# Sheet5.net
KiCad netlist of a schematic drawn in Altium Designer
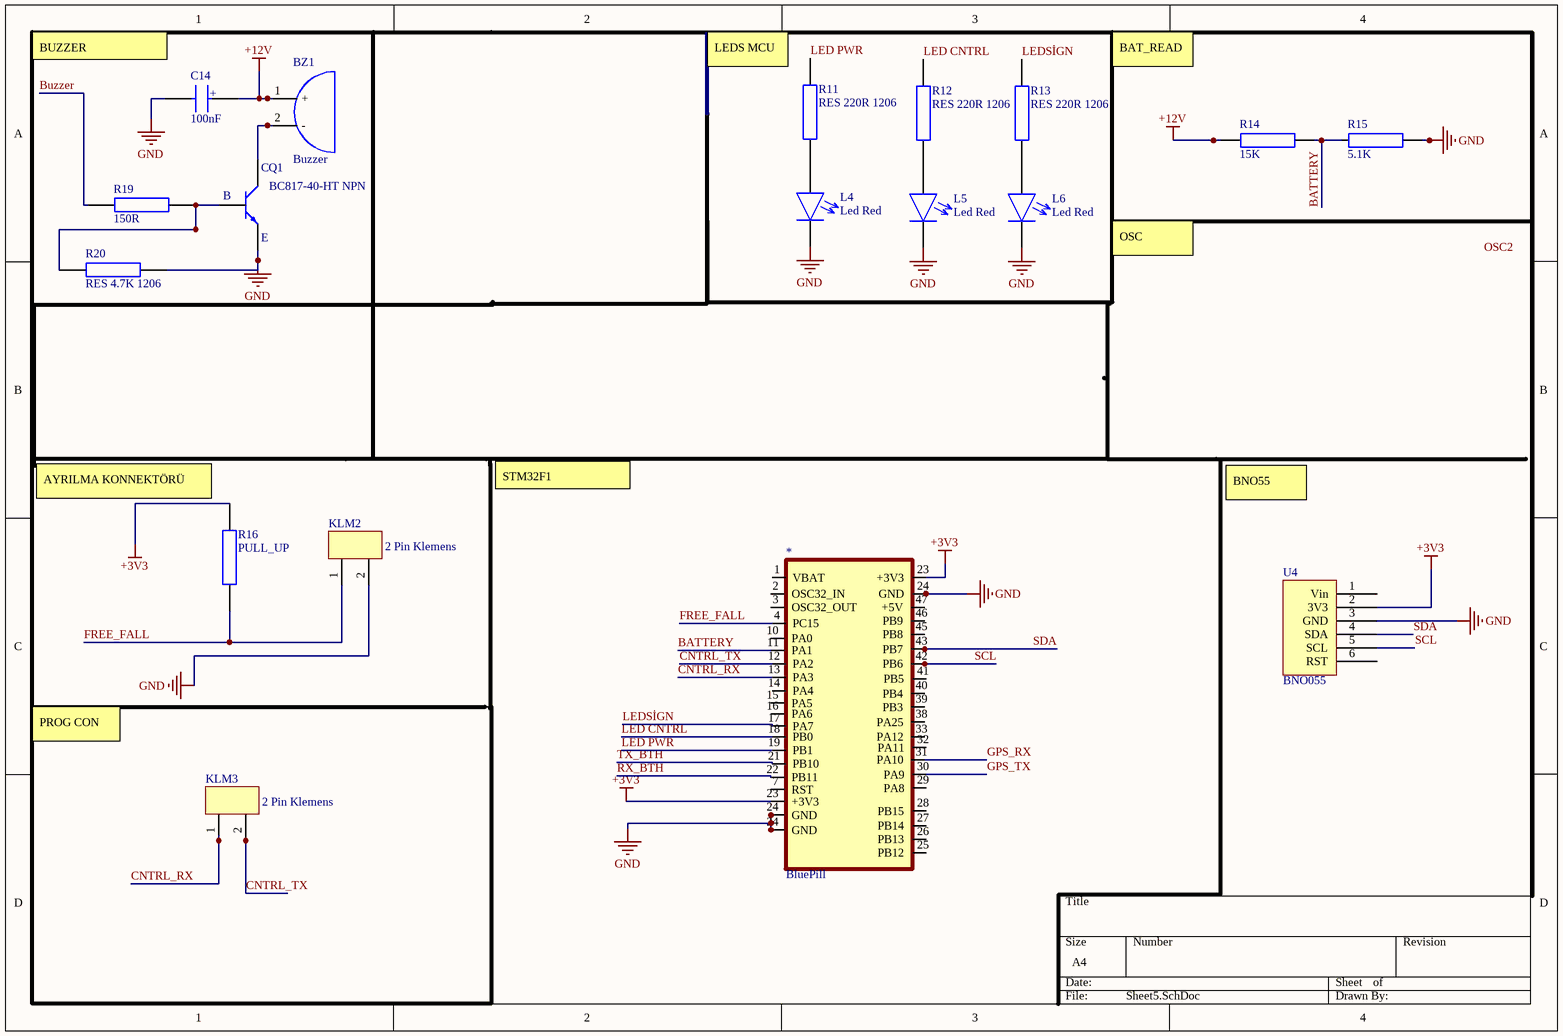
[diagram p0: Sheet5.SchDoc]

(export (version "E")
  (design (tool "Eeschema 10.0.6"))
  (components
    (comp (ref "*") (value "BluePill") (footprint "BLUEPILL") (libsource (lib "Schlib") (part "BluePill")))
    (comp (ref "BZ1")
      (value "Buzzer")
      (footprint "CMI-9605IC")
      (fields (field (name "DESIGNED BY") "Ahmet Azboy"))
      (libsource (lib "Udemy_Schlib1") (part "BUZZER"))
    )
    (comp (ref "C14")
      (value "100nF")
      (footprint "CAP_805")
      (description "0805 smd")
      (libsource (lib "Udemy_Schlib1") (part "CAP 100nF 0805"))
    )
    (comp (ref "KLM2")
      (value "2 Pin Klemens")
      (footprint "5.08mm-2 pin")
      (description "5.08mm 2 pin klemens")
      (libsource (lib "Udemy_Schlib1") (part "2 Pin Klemens"))
    )
    (comp (ref "KLM3")
      (value "2 Pin Klemens")
      (footprint "5.08mm-2 pin")
      (description "5.08mm 2 pin klemens")
      (libsource (lib "Udemy_Schlib1") (part "2 Pin Klemens"))
    )
    (comp (ref "L4")
      (value "Led Red")
      (footprint "Led 1206")
      (libsource (lib "Udemy_Schlib1") (part "Led Red"))
    )
    (comp (ref "L5")
      (value "Led Red")
      (footprint "Led 1206")
      (libsource (lib "Udemy_Schlib1") (part "Led Red"))
    )
    (comp (ref "L6")
      (value "Led Red")
      (footprint "Led 1206")
      (libsource (lib "Udemy_Schlib1") (part "Led Red"))
    )
    (comp (ref "Q1")
      (value "BC817-40-HT NPN")
      (footprint "SOT-23")
      (fields (field (name "VOLTAGE") "45V"))
      (libsource (lib "Udemy_Schlib1") (part "BC817-40-HT NPN"))
    )
    (comp (ref "R11")
      (value "RES 220R 1206")
      (footprint "RES_1206")
      (libsource (lib "Udemy_Schlib1") (part "RES 220R 1206"))
    )
    (comp (ref "R12")
      (value "RES 220R 1206")
      (footprint "RES_1206")
      (libsource (lib "Udemy_Schlib1") (part "RES 220R 1206"))
    )
    (comp (ref "R13")
      (value "RES 220R 1206")
      (footprint "RES_1206")
      (libsource (lib "Udemy_Schlib1") (part "RES 220R 1206"))
    )
    (comp (ref "R14")
      (value "15K")
      (footprint "RES_1206")
      (libsource (lib "Udemy_Schlib1") (part "RES 1K 1206"))
    )
    (comp (ref "R15")
      (value "5.1K")
      (footprint "RES_1206")
      (libsource (lib "Udemy_Schlib1") (part "RES 1K 1206"))
    )
    (comp (ref "R16")
      (value "PULL_UP")
      (footprint "RES_1206")
      (libsource (lib "Udemy_Schlib1") (part "RES 4.7K 1206"))
    )
    (comp (ref "R19")
      (value "150R")
      (footprint "RES_1206")
      (libsource (lib "Udemy_Schlib1") (part "RES 4.7K 1206"))
    )
    (comp (ref "R20")
      (value "RES 4.7K 1206")
      (footprint "RES_1206")
      (libsource (lib "Udemy_Schlib1") (part "RES 4.7K 1206"))
    )
    (comp (ref "U4") (value "BNO055") (footprint "BNO055") (libsource (lib "Schlib") (part "BNO055")))
  )
  (nets
    (net (code "1") (name "+3V3") (class "Default")
      (node (ref "*") (pin "23") (pinfunction "+3V3_23") (pintype "passive"))
      (node (ref "R16") (pin "2") (pintype "passive"))
      (node (ref "U4") (pin "2") (pinfunction "3V3_2") (pintype "passive"))
    )
    (net (code "2") (name "+12V") (class "Default")
      (node (ref "BZ1") (pin "1") (pinfunction "+_1") (pintype "passive"))
      (node (ref "C14") (pin "1") (pinfunction "1_1") (pintype "passive"))
      (node (ref "R14") (pin "1") (pintype "passive"))
    )
    (net (code "3") (name "/BATTERY") (class "Default")
      (node (ref "*") (pin "11") (pinfunction "PA1_11") (pintype "passive"))
      (node (ref "R14") (pin "2") (pintype "passive"))
      (node (ref "R15") (pin "1") (pintype "passive"))
    )
    (net (code "4") (name "/Buzzer") (class "Default") (node (ref "R19") (pin "2") (pintype "passive")))
    (net (code "5") (name "/CNTRL_RX") (class "Default")
      (node (ref "*") (pin "13") (pinfunction "PA3_13") (pintype "passive"))
      (node (ref "KLM3") (pin "1") (pintype "passive"))
    )
    (net (code "6") (name "/CNTRL_TX") (class "Default")
      (node (ref "*") (pin "12") (pinfunction "PA2_12") (pintype "passive"))
      (node (ref "KLM3") (pin "2") (pintype "passive"))
    )
    (net (code "7") (name "/FREE_FALL") (class "Default")
      (node (ref "*") (pin "4") (pinfunction "PC15_4") (pintype "passive"))
      (node (ref "KLM2") (pin "1") (pintype "passive"))
      (node (ref "R16") (pin "1") (pintype "passive"))
    )
    (net (code "8") (name "/GPS_RX") (class "Default")
      (node (ref "*") (pin "31") (pinfunction "PA10_31") (pintype "passive"))
    )
    (net (code "9") (name "/GPS_TX") (class "Default")
      (node (ref "*") (pin "30") (pinfunction "PA9_30") (pintype "passive"))
    )
    (net (code "10") (name "/LED CNTRL") (class "Default")
      (node (ref "*") (pin "18") (pinfunction "PB0_18") (pintype "passive"))
      (node (ref "R12") (pin "2") (pintype "passive"))
    )
    (net (code "11") (name "/LED PWR") (class "Default")
      (node (ref "*") (pin "19") (pinfunction "PB1_19") (pintype "passive"))
      (node (ref "R11") (pin "2") (pintype "passive"))
    )
    (net (code "12") (name "/LEDSİGN") (class "Default")
      (node (ref "*") (pin "17") (pinfunction "PA7_17") (pintype "passive"))
      (node (ref "R13") (pin "2") (pintype "passive"))
    )
    (net (code "14") (name "/RX_BTH") (class "Default")
      (node (ref "*") (pin "22") (pinfunction "PB11_22") (pintype "passive"))
    )
    (net (code "15") (name "/SCL") (class "Default")
      (node (ref "*") (pin "42") (pinfunction "PB6_42") (pintype "passive"))
      (node (ref "U4") (pin "5") (pinfunction "SCL_5") (pintype "passive"))
    )
    (net (code "16") (name "/SDA") (class "Default")
      (node (ref "*") (pin "43") (pinfunction "PB7_43") (pintype "passive"))
      (node (ref "U4") (pin "4") (pinfunction "SDA_4") (pintype "passive"))
    )
    (net (code "17") (name "/TX_BTH") (class "Default")
      (node (ref "*") (pin "21") (pinfunction "PB10_21") (pintype "passive"))
    )
    (net (code "18") (name "GND") (class "Default")
      (node (ref "*") (pin "24") (pinfunction "GND_24") (pintype "passive"))
      (node (ref "C14") (pin "2") (pinfunction "2_2") (pintype "passive"))
      (node (ref "KLM2") (pin "2") (pintype "passive"))
      (node (ref "L4") (pin "2") (pintype "passive"))
      (node (ref "L5") (pin "2") (pintype "passive"))
      (node (ref "L6") (pin "2") (pintype "passive"))
      (node (ref "Q1") (pin "2") (pintype "passive"))
      (node (ref "R15") (pin "2") (pintype "passive"))
      (node (ref "R20") (pin "1") (pintype "passive"))
      (node (ref "U4") (pin "3") (pinfunction "GND_3") (pintype "passive"))
    )
    (net (code "19") (name "Net-(BZ1--)") (class "Default")
      (node (ref "BZ1") (pin "2") (pinfunction "-_2") (pintype "passive"))
      (node (ref "Q1") (pin "3") (pintype "passive"))
    )
    (net (code "20") (name "Net-(L4-Pad1)") (class "Default")
      (node (ref "L4") (pin "1") (pintype "passive"))
      (node (ref "R11") (pin "1") (pintype "passive"))
    )
    (net (code "21") (name "Net-(L5-Pad1)") (class "Default")
      (node (ref "L5") (pin "1") (pintype "passive"))
      (node (ref "R12") (pin "1") (pintype "passive"))
    )
    (net (code "22") (name "Net-(L6-Pad1)") (class "Default")
      (node (ref "L6") (pin "1") (pintype "passive"))
      (node (ref "R13") (pin "1") (pintype "passive"))
    )
    (net (code "23") (name "Net-(Q1-Pad1)") (class "Default")
      (node (ref "Q1") (pin "1") (pintype "passive"))
      (node (ref "R19") (pin "1") (pintype "passive"))
      (node (ref "R20") (pin "2") (pintype "passive"))
    )
    (net (code "24") (name "unconnected-(*-+5V-Pad47)") (class "Default")
      (node (ref "*") (pin "47") (pinfunction "+5V_47") (pintype "passive"))
    )
    (net (code "25") (name "unconnected-(*-OSC32_IN-Pad2)") (class "Default")
      (node (ref "*") (pin "2") (pinfunction "OSC32_IN_2") (pintype "passive"))
    )
    (net (code "26") (name "unconnected-(*-OSC32_OUT-Pad3)") (class "Default")
      (node (ref "*") (pin "3") (pinfunction "OSC32_OUT_3") (pintype "passive"))
    )
    (net (code "27") (name "unconnected-(*-PA0-Pad10)") (class "Default")
      (node (ref "*") (pin "10") (pinfunction "PA0_10") (pintype "passive"))
    )
    (net (code "28") (name "unconnected-(*-PA4-Pad14)") (class "Default")
      (node (ref "*") (pin "14") (pinfunction "PA4_14") (pintype "passive"))
    )
    (net (code "29") (name "unconnected-(*-PA5-Pad15)") (class "Default")
      (node (ref "*") (pin "15") (pinfunction "PA5_15") (pintype "passive"))
    )
    (net (code "30") (name "unconnected-(*-PA6-Pad16)") (class "Default")
      (node (ref "*") (pin "16") (pinfunction "PA6_16") (pintype "passive"))
    )
    (net (code "31") (name "unconnected-(*-PA8-Pad29)") (class "Default")
      (node (ref "*") (pin "29") (pinfunction "PA8_29") (pintype "passive"))
    )
    (net (code "32") (name "unconnected-(*-PA11-Pad32)") (class "Default")
      (node (ref "*") (pin "32") (pinfunction "PA11_32") (pintype "passive"))
    )
    (net (code "33") (name "unconnected-(*-PA12-Pad33)") (class "Default")
      (node (ref "*") (pin "33") (pinfunction "PA12_33") (pintype "passive"))
    )
    (net (code "34") (name "unconnected-(*-PA25-Pad38)") (class "Default")
      (node (ref "*") (pin "38") (pinfunction "PA25_38") (pintype "passive"))
    )
    (net (code "35") (name "unconnected-(*-PB3-Pad39)") (class "Default")
      (node (ref "*") (pin "39") (pinfunction "PB3_39") (pintype "passive"))
    )
    (net (code "36") (name "unconnected-(*-PB4-Pad40)") (class "Default")
      (node (ref "*") (pin "40") (pinfunction "PB4_40") (pintype "passive"))
    )
    (net (code "37") (name "unconnected-(*-PB5-Pad41)") (class "Default")
      (node (ref "*") (pin "41") (pinfunction "PB5_41") (pintype "passive"))
    )
    (net (code "38") (name "unconnected-(*-PB8-Pad45)") (class "Default")
      (node (ref "*") (pin "45") (pinfunction "PB8_45") (pintype "passive"))
    )
    (net (code "39") (name "unconnected-(*-PB9-Pad46)") (class "Default")
      (node (ref "*") (pin "46") (pinfunction "PB9_46") (pintype "passive"))
    )
    (net (code "40") (name "unconnected-(*-PB12-Pad25)") (class "Default")
      (node (ref "*") (pin "25") (pinfunction "PB12_25") (pintype "passive"))
    )
    (net (code "41") (name "unconnected-(*-PB13-Pad26)") (class "Default")
      (node (ref "*") (pin "26") (pinfunction "PB13_26") (pintype "passive"))
    )
    (net (code "42") (name "unconnected-(*-PB14-Pad27)") (class "Default")
      (node (ref "*") (pin "27") (pinfunction "PB14_27") (pintype "passive"))
    )
    (net (code "43") (name "unconnected-(*-PB15-Pad28)") (class "Default")
      (node (ref "*") (pin "28") (pinfunction "PB15_28") (pintype "passive"))
    )
    (net (code "44") (name "unconnected-(*-RST-Pad7)") (class "Default")
      (node (ref "*") (pin "7") (pinfunction "RST_7") (pintype "passive"))
    )
    (net (code "45") (name "unconnected-(*-VBAT-Pad1)") (class "Default")
      (node (ref "*") (pin "1") (pinfunction "VBAT_1") (pintype "passive"))
    )
    (net (code "46") (name "unconnected-(U4-RST-Pad6)") (class "Default")
      (node (ref "U4") (pin "6") (pinfunction "RST_6") (pintype "passive"))
    )
    (net (code "47") (name "unconnected-(U4-Vin-Pad1)") (class "Default")
      (node (ref "U4") (pin "1") (pinfunction "Vin_1") (pintype "passive"))
    )
  )
)
